# NUWC_Ballast_Sensor_Power_Interface_Boar.net
KiCad netlist of a schematic drawn in Altium Designer
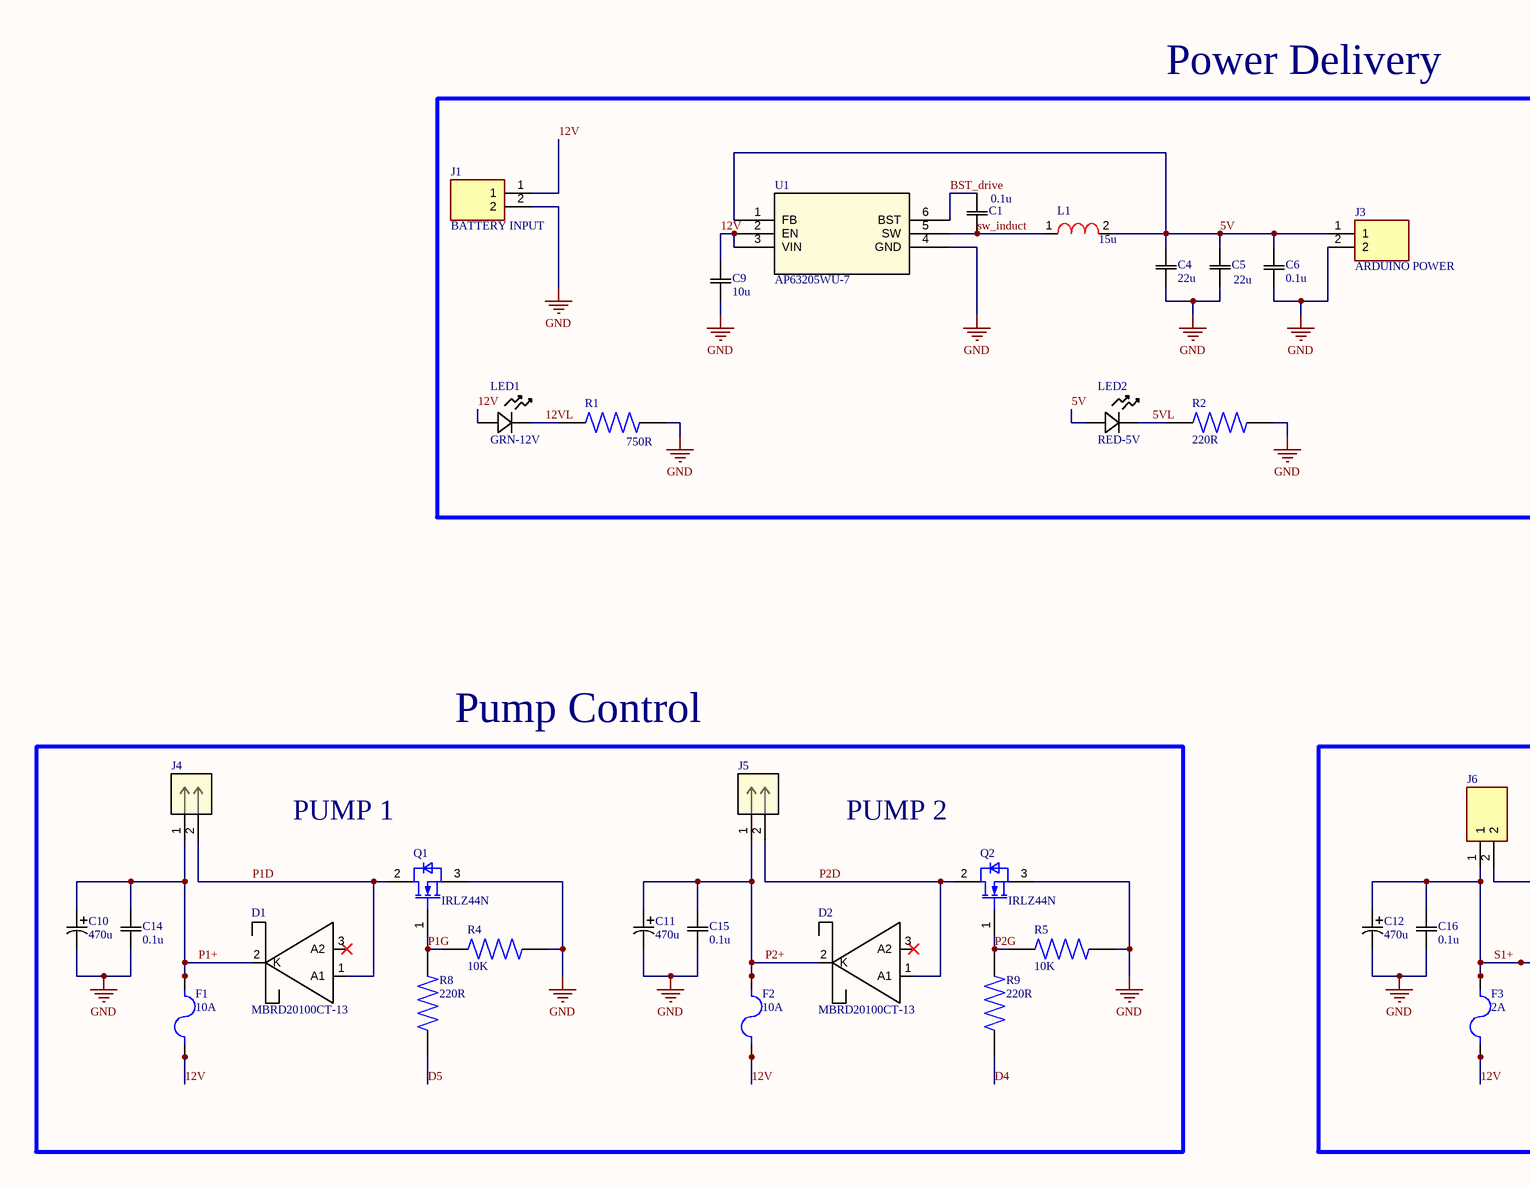
[diagram p0: NUWC_Ballast_Sensor_Power_Interface_Board.SchDoc, top left]
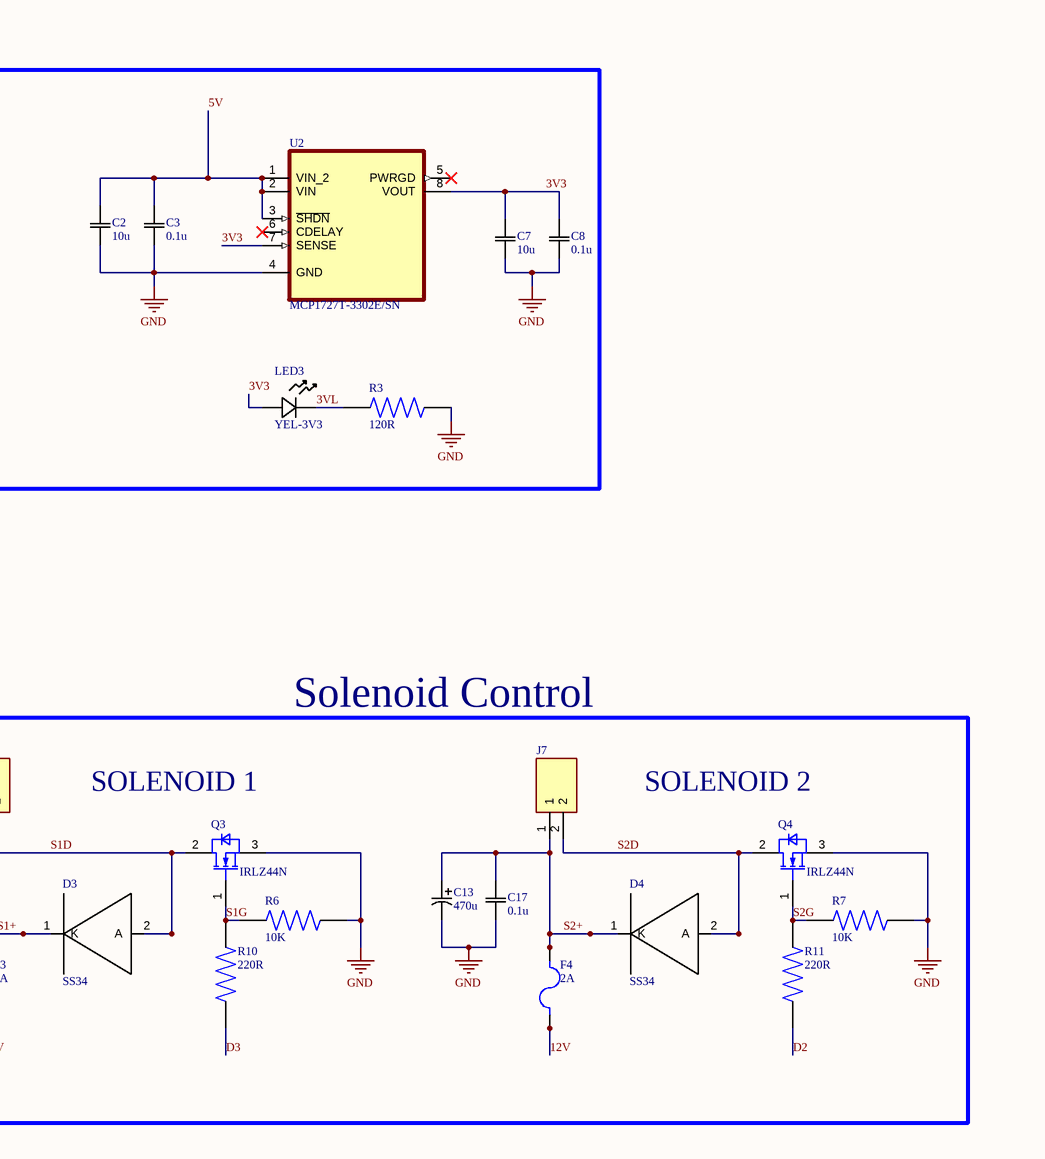
[diagram p1: NUWC_Ballast_Sensor_Power_Interface_Board.SchDoc, top right]
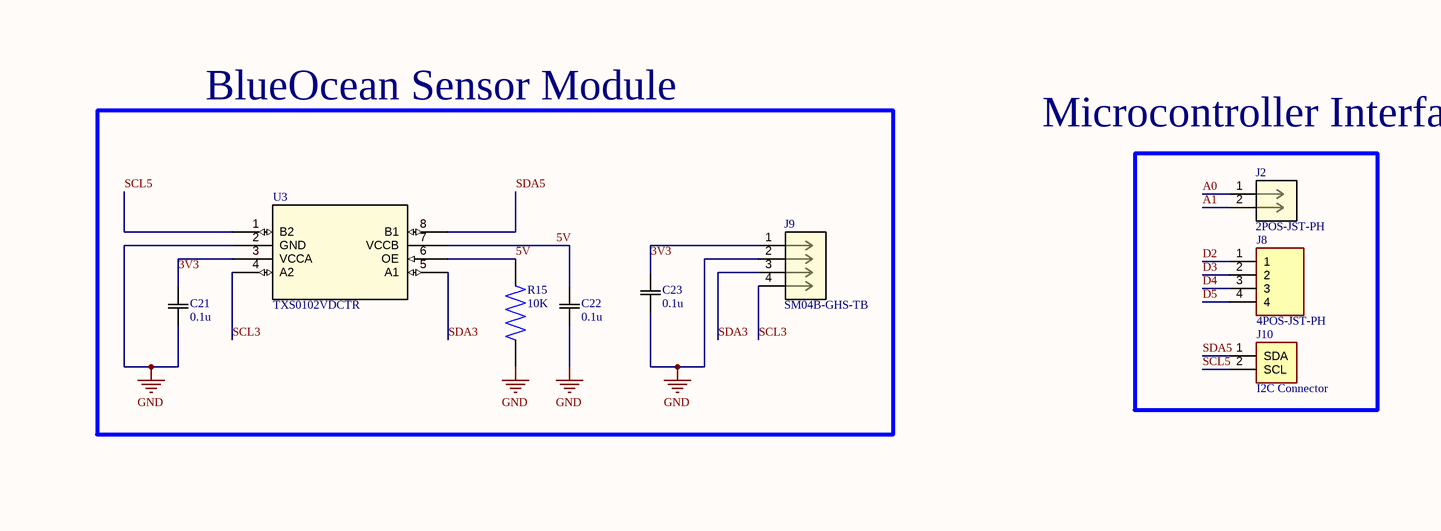
[diagram p2: NUWC_Ballast_Sensor_Power_Interface_Board.SchDoc, bottom left]
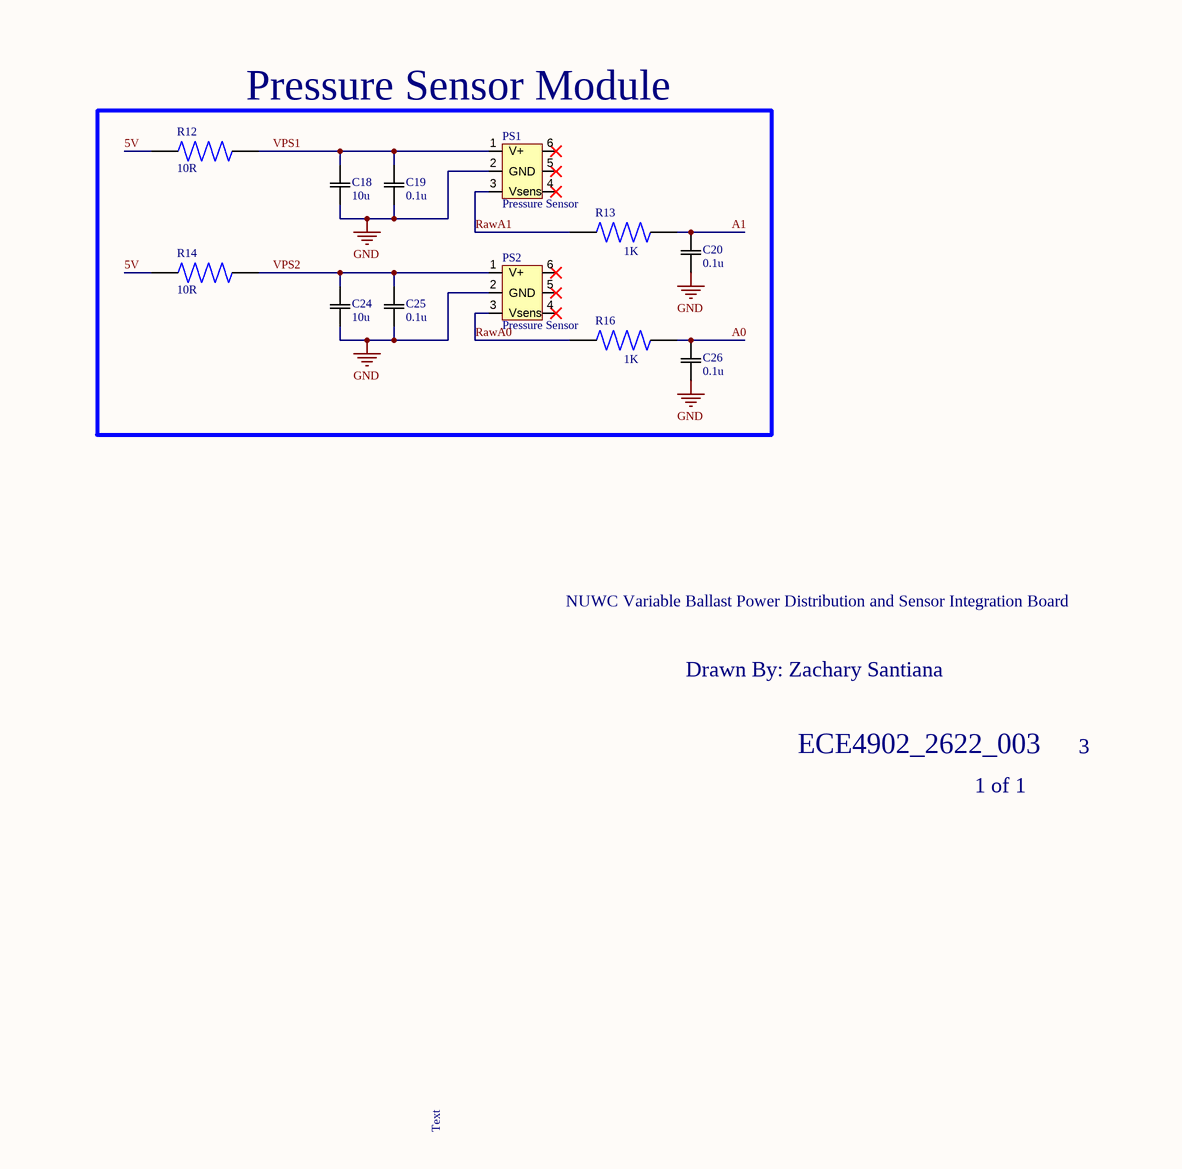
[diagram p3: NUWC_Ballast_Sensor_Power_Interface_Board.SchDoc, bottom right]

(export (version "E")
  (design (tool "Eeschema 10.0.6"))
  (components
    (comp (ref "C1")
      (value "0.1u")
      (footprint "CAP_0805_KEMET")
      (description "Capacitor;Ceramic;Cap;.0.1uF;Tol 10%;SMT;Vol-Rtg 25V;X7R;Tape and Reel ¦ KEMET C0805C104K3RACTU")
      (fields (field (name "MF") "KEMET") (field (name "MP") "C0805C104K3RACTU"))
      (libsource (lib "NUWCBallastBOMSymbols") (part "C0805C104K3RACTU"))
    )
    (comp (ref "C2")
      (value "10u")
      (footprint "CAP_0805_KEMET")
      (description "Capacitor;Ceramic;Cap;.10uF;Tol 10%;SMT;Vol-Rtg 25V;X5R;Tape and Reel ¦ KEMET C0805C106K3PACTU")
      (fields (field (name "MF") "KEMET") (field (name "MP") "C0805C106K3PACTU"))
      (libsource (lib "NUWCBallastBOMSymbols") (part "C0805C106K3PACTU"))
    )
    (comp (ref "C3")
      (value "0.1u")
      (footprint "CAP_0805_KEMET")
      (description "Capacitor;Ceramic;Cap;.0.1uF;Tol 10%;SMT;Vol-Rtg 25V;X7R;Tape and Reel ¦ KEMET C0805C104K3RACTU")
      (fields (field (name "MF") "KEMET") (field (name "MP") "C0805C104K3RACTU"))
      (libsource (lib "NUWCBallastBOMSymbols") (part "C0805C104K3RACTU"))
    )
    (comp (ref "C4")
      (value "22u")
      (footprint "CAP_0805_SAMSUNG")
      (description "Multilayer Ceramic Capacitors MLCC - SMD/SMT 22uF+/-20% 25V X5R 2012")
      (fields (field (name "MF") "Samsung Electro-Mechanics") (field (name "MP") "CL21A226MAYNNNE"))
      (libsource (lib "NUWCBallastBOMSymbols") (part "CL21A226MAYNNNE"))
    )
    (comp (ref "C5")
      (value "22u")
      (footprint "CAP_0805_SAMSUNG")
      (description "Multilayer Ceramic Capacitors MLCC - SMD/SMT 22uF+/-20% 25V X5R 2012")
      (fields (field (name "MF") "Samsung Electro-Mechanics") (field (name "MP") "CL21A226MAYNNNE"))
      (libsource (lib "NUWCBallastBOMSymbols") (part "CL21A226MAYNNNE"))
    )
    (comp (ref "C6")
      (value "0.1u")
      (footprint "CAP_0805_KEMET")
      (description "Capacitor;Ceramic;Cap;.0.1uF;Tol 10%;SMT;Vol-Rtg 25V;X7R;Tape and Reel ¦ KEMET C0805C104K3RACTU")
      (fields (field (name "MF") "KEMET") (field (name "MP") "C0805C104K3RACTU"))
      (libsource (lib "NUWCBallastBOMSymbols") (part "C0805C104K3RACTU"))
    )
    (comp (ref "C7")
      (value "10u")
      (footprint "CAP_0805_KEMET")
      (description "Capacitor;Ceramic;Cap;.10uF;Tol 10%;SMT;Vol-Rtg 25V;X5R;Tape and Reel ¦ KEMET C0805C106K3PACTU")
      (fields (field (name "MF") "KEMET") (field (name "MP") "C0805C106K3PACTU"))
      (libsource (lib "NUWCBallastBOMSymbols") (part "C0805C106K3PACTU"))
    )
    (comp (ref "C8")
      (value "0.1u")
      (footprint "CAP_0805_KEMET")
      (description "Capacitor;Ceramic;Cap;.0.1uF;Tol 10%;SMT;Vol-Rtg 25V;X7R;Tape and Reel ¦ KEMET C0805C104K3RACTU")
      (fields (field (name "MF") "KEMET") (field (name "MP") "C0805C104K3RACTU"))
      (libsource (lib "NUWCBallastBOMSymbols") (part "C0805C104K3RACTU"))
    )
    (comp (ref "C9")
      (value "10u")
      (footprint "CAP_0805_KEMET")
      (description "Capacitor;Ceramic;Cap;.10uF;Tol 10%;SMT;Vol-Rtg 25V;X5R;Tape and Reel ¦ KEMET C0805C106K3PACTU")
      (fields (field (name "MF") "KEMET") (field (name "MP") "C0805C106K3PACTU"))
      (libsource (lib "NUWCBallastBOMSymbols") (part "C0805C106K3PACTU"))
    )
    (comp (ref "C10")
      (value "470u")
      (footprint "PCAP_10x10-ELECT_NCA")
      (fields
        (field (name "MANUFACTURER_PART_NUMBER") "UWT1E471MNL1GS")
        (field (name "COPYRIGHT") "Copyright (C) 2025 Ultra Librarian. All rights reserved.")
      )
      (libsource (lib "NUWCBallastBOMSymbols") (part "UWT1E471MNL1GS_1"))
    )
    (comp (ref "C11")
      (value "470u")
      (footprint "PCAP_10x10-ELECT_NCA")
      (fields
        (field (name "MANUFACTURER_PART_NUMBER") "UWT1E471MNL1GS")
        (field (name "COPYRIGHT") "Copyright (C) 2025 Ultra Librarian. All rights reserved.")
      )
      (libsource (lib "NUWCBallastBOMSymbols") (part "UWT1E471MNL1GS_1"))
    )
    (comp (ref "C12")
      (value "470u")
      (footprint "PCAP_10x10-ELECT_NCA")
      (fields
        (field (name "MANUFACTURER_PART_NUMBER") "UWT1E471MNL1GS")
        (field (name "COPYRIGHT") "Copyright (C) 2025 Ultra Librarian. All rights reserved.")
      )
      (libsource (lib "NUWCBallastBOMSymbols") (part "UWT1E471MNL1GS_1"))
    )
    (comp (ref "C13")
      (value "470u")
      (footprint "PCAP_10x10-ELECT_NCA")
      (fields
        (field (name "MANUFACTURER_PART_NUMBER") "UWT1E471MNL1GS")
        (field (name "COPYRIGHT") "Copyright (C) 2025 Ultra Librarian. All rights reserved.")
      )
      (libsource (lib "NUWCBallastBOMSymbols") (part "UWT1E471MNL1GS_1"))
    )
    (comp (ref "C14")
      (value "0.1u")
      (footprint "CAP_0805_KEMET")
      (description "Capacitor;Ceramic;Cap;.0.1uF;Tol 10%;SMT;Vol-Rtg 25V;X7R;Tape and Reel ¦ KEMET C0805C104K3RACTU")
      (fields (field (name "MF") "KEMET") (field (name "MP") "C0805C104K3RACTU"))
      (libsource (lib "NUWCBallastBOMSymbols") (part "C0805C104K3RACTU"))
    )
    (comp (ref "C15")
      (value "0.1u")
      (footprint "CAP_0805_KEMET")
      (description "Capacitor;Ceramic;Cap;.0.1uF;Tol 10%;SMT;Vol-Rtg 25V;X7R;Tape and Reel ¦ KEMET C0805C104K3RACTU")
      (fields (field (name "MF") "KEMET") (field (name "MP") "C0805C104K3RACTU"))
      (libsource (lib "NUWCBallastBOMSymbols") (part "C0805C104K3RACTU"))
    )
    (comp (ref "C16")
      (value "0.1u")
      (footprint "CAP_0805_KEMET")
      (description "Capacitor;Ceramic;Cap;.0.1uF;Tol 10%;SMT;Vol-Rtg 25V;X7R;Tape and Reel ¦ KEMET C0805C104K3RACTU")
      (fields (field (name "MF") "KEMET") (field (name "MP") "C0805C104K3RACTU"))
      (libsource (lib "NUWCBallastBOMSymbols") (part "C0805C104K3RACTU"))
    )
    (comp (ref "C17")
      (value "0.1u")
      (footprint "CAP_0805_KEMET")
      (description "Capacitor;Ceramic;Cap;.0.1uF;Tol 10%;SMT;Vol-Rtg 25V;X7R;Tape and Reel ¦ KEMET C0805C104K3RACTU")
      (fields (field (name "MF") "KEMET") (field (name "MP") "C0805C104K3RACTU"))
      (libsource (lib "NUWCBallastBOMSymbols") (part "C0805C104K3RACTU"))
    )
    (comp (ref "C18")
      (value "10u")
      (footprint "CAP_0805_KEMET")
      (description "Capacitor;Ceramic;Cap;.10uF;Tol 10%;SMT;Vol-Rtg 25V;X5R;Tape and Reel ¦ KEMET C0805C106K3PACTU")
      (fields (field (name "MF") "KEMET") (field (name "MP") "C0805C106K3PACTU"))
      (libsource (lib "NUWCBallastBOMSymbols") (part "C0805C106K3PACTU"))
    )
    (comp (ref "C19")
      (value "0.1u")
      (footprint "CAP_0805_KEMET")
      (description "Capacitor;Ceramic;Cap;.0.1uF;Tol 10%;SMT;Vol-Rtg 25V;X7R;Tape and Reel ¦ KEMET C0805C104K3RACTU")
      (fields (field (name "MF") "KEMET") (field (name "MP") "C0805C104K3RACTU"))
      (libsource (lib "NUWCBallastBOMSymbols") (part "C0805C104K3RACTU"))
    )
    (comp (ref "C20")
      (value "0.1u")
      (footprint "CAP_0805_KEMET")
      (description "Capacitor;Ceramic;Cap;.0.1uF;Tol 10%;SMT;Vol-Rtg 25V;X7R;Tape and Reel ¦ KEMET C0805C104K3RACTU")
      (fields (field (name "MF") "KEMET") (field (name "MP") "C0805C104K3RACTU"))
      (libsource (lib "NUWCBallastBOMSymbols") (part "C0805C104K3RACTU"))
    )
    (comp (ref "C21")
      (value "0.1u")
      (footprint "CAP_0805_KEMET")
      (description "Capacitor;Ceramic;Cap;.0.1uF;Tol 10%;SMT;Vol-Rtg 25V;X7R;Tape and Reel ¦ KEMET C0805C104K3RACTU")
      (fields (field (name "MF") "KEMET") (field (name "MP") "C0805C104K3RACTU"))
      (libsource (lib "NUWCBallastBOMSymbols") (part "C0805C104K3RACTU"))
    )
    (comp (ref "C22")
      (value "0.1u")
      (footprint "CAP_0805_KEMET")
      (description "Capacitor;Ceramic;Cap;.0.1uF;Tol 10%;SMT;Vol-Rtg 25V;X7R;Tape and Reel ¦ KEMET C0805C104K3RACTU")
      (fields (field (name "MF") "KEMET") (field (name "MP") "C0805C104K3RACTU"))
      (libsource (lib "NUWCBallastBOMSymbols") (part "C0805C104K3RACTU"))
    )
    (comp (ref "C23")
      (value "0.1u")
      (footprint "CAP_0805_KEMET")
      (description "Capacitor;Ceramic;Cap;.0.1uF;Tol 10%;SMT;Vol-Rtg 25V;X7R;Tape and Reel ¦ KEMET C0805C104K3RACTU")
      (fields (field (name "MF") "KEMET") (field (name "MP") "C0805C104K3RACTU"))
      (libsource (lib "NUWCBallastBOMSymbols") (part "C0805C104K3RACTU"))
    )
    (comp (ref "C24")
      (value "10u")
      (footprint "CAP_0805_KEMET")
      (description "Capacitor;Ceramic;Cap;.10uF;Tol 10%;SMT;Vol-Rtg 25V;X5R;Tape and Reel ¦ KEMET C0805C106K3PACTU")
      (fields (field (name "MF") "KEMET") (field (name "MP") "C0805C106K3PACTU"))
      (libsource (lib "NUWCBallastBOMSymbols") (part "C0805C106K3PACTU"))
    )
    (comp (ref "C25")
      (value "0.1u")
      (footprint "CAP_0805_KEMET")
      (description "Capacitor;Ceramic;Cap;.0.1uF;Tol 10%;SMT;Vol-Rtg 25V;X7R;Tape and Reel ¦ KEMET C0805C104K3RACTU")
      (fields (field (name "MF") "KEMET") (field (name "MP") "C0805C104K3RACTU"))
      (libsource (lib "NUWCBallastBOMSymbols") (part "C0805C104K3RACTU"))
    )
    (comp (ref "C26")
      (value "0.1u")
      (footprint "CAP_0805_KEMET")
      (description "Capacitor;Ceramic;Cap;.0.1uF;Tol 10%;SMT;Vol-Rtg 25V;X7R;Tape and Reel ¦ KEMET C0805C104K3RACTU")
      (fields (field (name "MF") "KEMET") (field (name "MP") "C0805C104K3RACTU"))
      (libsource (lib "NUWCBallastBOMSymbols") (part "C0805C104K3RACTU"))
    )
    (comp (ref "D1")
      (value "MBRD20100CT-13")
      (footprint "MBRD20100CT_SHOT_DIODE")
      (description "DIODE ARR SCHOT 100V 10A TO2523\r\nDiodes Incorporated")
      (libsource (lib "NUWCBallastBOMSymbols") (part "MBRD20100CT-13"))
    )
    (comp (ref "D2")
      (value "MBRD20100CT-13")
      (footprint "MBRD20100CT_SHOT_DIODE")
      (description "DIODE ARR SCHOT 100V 10A TO2523\r\nDiodes Incorporated")
      (libsource (lib "NUWCBallastBOMSymbols") (part "MBRD20100CT-13"))
    )
    (comp (ref "D3")
      (value "SS34")
      (footprint "SHOTT_DIODE")
      (description "Description")
      (fields (field (name "COPYRIGHT") "Copyright (C) 2025 Ultra Librarian. All rights reserved."))
      (libsource (lib "NUWCBallastBOMSymbols") (part "SS34"))
    )
    (comp (ref "D4")
      (value "SS34")
      (footprint "SHOTT_DIODE")
      (description "Description")
      (fields (field (name "COPYRIGHT") "Copyright (C) 2025 Ultra Librarian. All rights reserved."))
      (libsource (lib "NUWCBallastBOMSymbols") (part "SS34"))
    )
    (comp (ref "F1")
      (value "10A")
      (footprint "FUSE_3557-2")
      (description "THM 2 in 1 Auto Blade Holder")
      (fields (field (name "MF") "Keystone Electronics") (field (name "MP") "3557-2"))
      (libsource (lib "NUWCBallastBOMSymbols") (part "3557-2"))
    )
    (comp (ref "F2")
      (value "10A")
      (footprint "FUSE_3557-2")
      (description "THM 2 in 1 Auto Blade Holder")
      (fields (field (name "MF") "Keystone Electronics") (field (name "MP") "3557-2"))
      (libsource (lib "NUWCBallastBOMSymbols") (part "3557-2"))
    )
    (comp (ref "F3")
      (value "2A")
      (footprint "FUSE_3557-2")
      (description "THM 2 in 1 Auto Blade Holder")
      (fields (field (name "MF") "Keystone Electronics") (field (name "MP") "3557-2"))
      (libsource (lib "NUWCBallastBOMSymbols") (part "3557-2"))
    )
    (comp (ref "F4")
      (value "2A")
      (footprint "FUSE_3557-2")
      (description "THM 2 in 1 Auto Blade Holder")
      (fields (field (name "MF") "Keystone Electronics") (field (name "MP") "3557-2"))
      (libsource (lib "NUWCBallastBOMSymbols") (part "3557-2"))
    )
    (comp (ref "J1")
      (value "BATTERY INPUT")
      (footprint "CUI_TBP02R1-381-02BE")
      (description "2~24 Poles, Pluggable,Receptacle, Horizontal, 3.81 Pitch, Terminal Block Connector")
      (fields (field (name "MF") "Same Sky") (field (name "MP") "TBP02R1-381-02BE"))
      (libsource (lib "") (part "TBP02R1-381-02BE_1"))
    )
    (comp (ref "J2")
      (value "2POS-JST-PH")
      (footprint "JST_S2B-PH-SM4-TB")
      (libsource (lib "NUWCBallastBOMSymbols") (part "JST_PH_2POS_SMD_RA"))
    )
    (comp (ref "J3")
      (value "ARDUINO POWER")
      (footprint "CUI_TBP02R1-381-02BE")
      (description "2~24 Poles, Pluggable,Receptacle, Horizontal, 3.81 Pitch, Terminal Block Connector")
      (fields (field (name "MF") "Same Sky") (field (name "MP") "TBP02R1-381-02BE"))
      (libsource (lib "NUWCBallastBOMSymbols") (part "TBP02R1-381-02BE"))
    )
    (comp (ref "J4")
      (value "26607020")
      (footprint "CONN_SD-42892-001_M450_02_MOL")
      (fields (field (name "COPYRIGHT") "Copyright (C) 2026 Ultra Librarian. All rights reserved."))
      (libsource (lib "NUWCBallastBOMSymbols") (part "26607020"))
    )
    (comp (ref "J5")
      (value "26607020")
      (footprint "CONN_SD-42892-001_M450_02_MOL")
      (fields (field (name "COPYRIGHT") "Copyright (C) 2026 Ultra Librarian. All rights reserved."))
      (libsource (lib "NUWCBallastBOMSymbols") (part "26607020"))
    )
    (comp (ref "J6")
      (value "BATTERY INPUT")
      (footprint "CUI_TBP02R1-381-02BE")
      (description "2~24 Poles, Pluggable,Receptacle, Horizontal, 3.81 Pitch, Terminal Block Connector")
      (fields (field (name "MF") "Same Sky") (field (name "MP") "TBP02R1-381-02BE"))
      (libsource (lib "") (part "TBP02R1-381-02BE_2"))
    )
    (comp (ref "J7")
      (value "BATTERY INPUT")
      (footprint "CUI_TBP02R1-381-02BE")
      (description "2~24 Poles, Pluggable,Receptacle, Horizontal, 3.81 Pitch, Terminal Block Connector")
      (fields (field (name "MF") "Same Sky") (field (name "MP") "TBP02R1-381-02BE"))
      (libsource (lib "") (part "TBP02R1-381-02BE_2"))
    )
    (comp (ref "J8")
      (value "4POS-JST-PH")
      (footprint "JST_S4B-PH-SM4-TB")
      (description "Connector Header Surface Mount, Right Angle 4 position 0.079 (2.00mm)")
      (fields (field (name "MF") "JST Sales") (field (name "MP") "S4B-PH-SM4-TB"))
      (libsource (lib "NUWCBallastBOMSymbols") (part "S4B-PH-SM4-TB"))
    )
    (comp (ref "J9")
      (value "SM04B-GHS-TB")
      (footprint "CONN_SM04B-GHS-TB_JST")
      (description "Description")
      (fields (field (name "COPYRIGHT") "Copyright (C) 2025 Ultra Librarian. All rights reserved."))
      (libsource (lib "NUWCBallastBOMSymbols") (part "SM04B-GHS-TB"))
    )
    (comp (ref "J10")
      (value "I2C Connector")
      (footprint "MOLEX_530470210")
      (description "Connector Header Through Hole 2 position 0.049 (1.25mm)")
      (fields (field (name "DIGI-KEY_PART_NUMBER") "WM1731-ND") (field (name "MP") "530470210"))
      (libsource (lib "NUWCBallastBOMSymbols") (part "I2C Connector"))
    )
    (comp (ref "L1")
      (value "15u")
      (footprint "inductor")
      (libsource (lib "NUWCBallastBOMSymbols") (part "Inductor"))
    )
    (comp (ref "LED1")
      (value "GRN-12V")
      (footprint "LED_LGR971-KN-1_OSR")
      (description "GREEN DIFF LED")
      (fields
        (field (name "MANUFACTURER_PART_NUMBER") "LGR971-KN-1")
        (field (name "COPYRIGHT") "Copyright (C) 2025 Ultra Librarian. All rights reserved.")
      )
      (libsource (lib "NUWCBallastBOMSymbols") (part "LGR971-KN-1"))
    )
    (comp (ref "LED2")
      (value "RED-5V")
      (footprint "LED_LGR971-KN-1_OSR")
      (description "RED DIFF LED")
      (fields
        (field (name "MANUFACTURER_PART_NUMBER") "LGR971-KN-1")
        (field (name "COPYRIGHT") "Copyright (C) 2025 Ultra Librarian. All rights reserved.")
      )
      (libsource (lib "NUWCBallastBOMSymbols") (part "LS R976-NR-1-0-20-R18"))
    )
    (comp (ref "LED3")
      (value "YEL-3V3")
      (footprint "LED_LGR971-KN-1_OSR")
      (description "YEL DIFF LED")
      (fields
        (field (name "MANUFACTURER_PART_NUMBER") "LGR971-KN-1")
        (field (name "COPYRIGHT") "Copyright (C) 2025 Ultra Librarian. All rights reserved.")
      )
      (libsource (lib "NUWCBallastBOMSymbols") (part "LY R976-PS-36-0-20-R18"))
    )
    (comp (ref "PS1")
      (value "Pressure Sensor")
      (footprint "PCBComponent_1")
      (libsource (lib "NUWCBallastBOMSymbols") (part "Pressure Sensor"))
    )
    (comp (ref "PS2")
      (value "Pressure Sensor")
      (footprint "PCBComponent_1")
      (libsource (lib "NUWCBallastBOMSymbols") (part "Pressure Sensor"))
    )
    (comp (ref "Q1")
      (value "IRLZ44N")
      (footprint "IFX-PG-TO220-3-904-1")
      (description "OptiMOS 3 Power-Transistor, VDS 100V")
      (fields (field (name "MANUFACTURER") "Infineon Technologies"))
      (libsource (lib "NUWCBallastBOMSymbols") (part "IRLZ44N"))
    )
    (comp (ref "Q2")
      (value "IRLZ44N")
      (footprint "IFX-PG-TO220-3-904-1")
      (description "OptiMOS 3 Power-Transistor, VDS 100V")
      (fields (field (name "MANUFACTURER") "Infineon Technologies"))
      (libsource (lib "NUWCBallastBOMSymbols") (part "IRLZ44N"))
    )
    (comp (ref "Q3")
      (value "IRLZ44N")
      (footprint "IFX-PG-TO220-3-904-1")
      (description "OptiMOS 3 Power-Transistor, VDS 100V")
      (fields (field (name "MANUFACTURER") "Infineon Technologies"))
      (libsource (lib "NUWCBallastBOMSymbols") (part "IRLZ44N"))
    )
    (comp (ref "Q4")
      (value "IRLZ44N")
      (footprint "IFX-PG-TO220-3-904-1")
      (description "OptiMOS 3 Power-Transistor, VDS 100V")
      (fields (field (name "MANUFACTURER") "Infineon Technologies"))
      (libsource (lib "NUWCBallastBOMSymbols") (part "IRLZ44N"))
    )
    (comp (ref "R1")
      (value "750R")
      (footprint "RESC2012X50N")
      (fields (field (name "MF") "Vishay") (field (name "MP") "CRCW08051K00FKEA"))
      (libsource (lib "NUWCBallastBOMSymbols") (part "CRCW08051K00FKEA"))
    )
    (comp (ref "R2")
      (value "220R")
      (footprint "RESC2012X50N")
      (fields
        (field (name "MF") "Vishay")
        (field (name "MP") "CRCW08051K00FKEA")
        (field (name "Comment") "CRCW0805560RFKEA")
      )
      (libsource (lib "NUWCBallastBOMSymbols") (part "CRCW0805560RFKEA"))
    )
    (comp (ref "R3")
      (value "120R")
      (footprint "RESC2012X50N")
      (fields
        (field (name "MF") "Vishay")
        (field (name "MP") "CRCW08051K00FKEA")
        (field (name "Comment") "CRCW0805120RFKEA")
      )
      (libsource (lib "NUWCBallastBOMSymbols") (part "CRCW0805120RFKEA"))
    )
    (comp (ref "R4")
      (value "10K")
      (footprint "RESC2012X50N")
      (fields
        (field (name "MF") "Vishay")
        (field (name "MP") "CRCW08051K00FKEA")
        (field (name "Comment") "CRCW080510K0FKEA")
      )
      (libsource (lib "NUWCBallastBOMSymbols") (part "CRCW080510K0FKEA"))
    )
    (comp (ref "R5")
      (value "10K")
      (footprint "RESC2012X50N")
      (fields
        (field (name "MF") "Vishay")
        (field (name "MP") "CRCW08051K00FKEA")
        (field (name "Comment") "CRCW080510K0FKEA")
      )
      (libsource (lib "NUWCBallastBOMSymbols") (part "CRCW080510K0FKEA"))
    )
    (comp (ref "R6")
      (value "10K")
      (footprint "RESC2012X50N")
      (fields
        (field (name "MF") "Vishay")
        (field (name "MP") "CRCW08051K00FKEA")
        (field (name "Comment") "CRCW080510K0FKEA")
      )
      (libsource (lib "NUWCBallastBOMSymbols") (part "CRCW080510K0FKEA"))
    )
    (comp (ref "R7")
      (value "10K")
      (footprint "RESC2012X50N")
      (fields
        (field (name "MF") "Vishay")
        (field (name "MP") "CRCW08051K00FKEA")
        (field (name "Comment") "CRCW080510K0FKEA")
      )
      (libsource (lib "NUWCBallastBOMSymbols") (part "CRCW080510K0FKEA"))
    )
    (comp (ref "R8")
      (value "220R")
      (footprint "RESC2012X50N")
      (fields
        (field (name "MF") "Vishay")
        (field (name "MP") "CRCW08051K00FKEA")
        (field (name "Comment") "CRCW0805220RFKEA")
      )
      (libsource (lib "NUWCBallastBOMSymbols") (part "CRCW0805220RFKEA"))
    )
    (comp (ref "R9")
      (value "220R")
      (footprint "RESC2012X50N")
      (fields
        (field (name "MF") "Vishay")
        (field (name "MP") "CRCW08051K00FKEA")
        (field (name "Comment") "CRCW0805220RFKEA")
      )
      (libsource (lib "NUWCBallastBOMSymbols") (part "CRCW0805220RFKEA"))
    )
    (comp (ref "R10")
      (value "220R")
      (footprint "RESC2012X50N")
      (fields
        (field (name "MF") "Vishay")
        (field (name "MP") "CRCW08051K00FKEA")
        (field (name "Comment") "CRCW0805220RFKEA")
      )
      (libsource (lib "NUWCBallastBOMSymbols") (part "CRCW0805220RFKEA"))
    )
    (comp (ref "R11")
      (value "220R")
      (footprint "RESC2012X50N")
      (fields
        (field (name "MF") "Vishay")
        (field (name "MP") "CRCW08051K00FKEA")
        (field (name "Comment") "CRCW0805220RFKEA")
      )
      (libsource (lib "NUWCBallastBOMSymbols") (part "CRCW0805220RFKEA"))
    )
    (comp (ref "R12")
      (value "10R")
      (footprint "RESC2012X50N")
      (fields
        (field (name "MF") "Vishay")
        (field (name "MP") "CRCW08051K00FKEA")
        (field (name "Comment") "CRCW080510R0FKEA")
      )
      (libsource (lib "NUWCBallastBOMSymbols") (part "CRCW080510R0FKEA"))
    )
    (comp (ref "R13")
      (value "1K")
      (footprint "RESC2012X50N")
      (fields (field (name "MF") "Vishay") (field (name "MP") "CRCW08051K00FKEA"))
      (libsource (lib "NUWCBallastBOMSymbols") (part "CRCW08051K00FKEA"))
    )
    (comp (ref "R14")
      (value "10R")
      (footprint "RESC2012X50N")
      (fields
        (field (name "MF") "Vishay")
        (field (name "MP") "CRCW08051K00FKEA")
        (field (name "Comment") "CRCW080510R0FKEA")
      )
      (libsource (lib "NUWCBallastBOMSymbols") (part "CRCW080510R0FKEA"))
    )
    (comp (ref "R15")
      (value "10K")
      (footprint "RESC2012X50N")
      (fields
        (field (name "MF") "Vishay")
        (field (name "MP") "CRCW08051K00FKEA")
        (field (name "Comment") "CRCW080510K0FKEA")
      )
      (libsource (lib "NUWCBallastBOMSymbols") (part "CRCW080510K0FKEA"))
    )
    (comp (ref "R16")
      (value "1K")
      (footprint "RESC2012X50N")
      (fields (field (name "MF") "Vishay") (field (name "MP") "CRCW08051K00FKEA"))
      (libsource (lib "NUWCBallastBOMSymbols") (part "CRCW08051K00FKEA"))
    )
    (comp (ref "U1")
      (value "AP63205WU-7")
      (footprint "SOIC_05WU-7_DIO")
      (description "Description")
      (fields (field (name "COPYRIGHT") "Copyright (C) 2025 Ultra Librarian. All rights reserved."))
      (libsource (lib "NUWCBallastBOMSymbols") (part "AP63205WU-7"))
    )
    (comp (ref "U2")
      (value "MCP1727T-3302E/SN")
      (footprint "SOIC127P490X175-8N")
      (description "1.5A CMOS LDO, Vout=3.3V, Extended Temp Range ¦ Microchip Technology Inc. MCP1727T-3302E/SN")
      (fields (field (name "MF") "Microchip Technology"))
      (libsource (lib "NUWCBallastBOMSymbols") (part "MCP1727T-3302E/SN"))
    )
    (comp (ref "U3")
      (value "TXS0102VDCTR")
      (footprint "SSOP8_DCT_TEX")
      (description "Two-bit bidirectional level shifter for open-drain and push-pull applications 8-SSOP -40 to 85")
      (fields (field (name "COPYRIGHT") "Copyright (C) 2025 Ultra Librarian. All rights reserved."))
      (libsource (lib "NUWCBallastBOMSymbols") (part "TXS0102VDCTR"))
    )
  )
  (nets
    (net (code "1") (name "/3V3") (class "Default")
      (node (ref "C21") (pin "2") (pinfunction "2_2") (pintype "passive"))
      (node (ref "C23") (pin "2") (pinfunction "2_2") (pintype "passive"))
      (node (ref "C7") (pin "2") (pinfunction "2_2") (pintype "passive"))
      (node (ref "C8") (pin "2") (pinfunction "2_2") (pintype "passive"))
      (node (ref "J9") (pin "1") (pinfunction "1_1") (pintype "passive"))
      (node (ref "LED3") (pin "2") (pinfunction "2_2") (pintype "passive"))
      (node (ref "U2") (pin "7") (pinfunction "SENSE_7") (pintype "input"))
      (node (ref "U2") (pin "8") (pinfunction "VOUT_8") (pintype "power_in"))
      (node (ref "U3") (pin "3") (pinfunction "VCCA_3") (pintype "power_in"))
    )
    (net (code "2") (name "/3VL") (class "Default")
      (node (ref "LED3") (pin "1") (pinfunction "1_1") (pintype "passive"))
      (node (ref "R3") (pin "1") (pinfunction "1_1") (pintype "passive"))
    )
    (net (code "3") (name "/5V") (class "Default")
      (node (ref "C2") (pin "2") (pinfunction "2_2") (pintype "passive"))
      (node (ref "C22") (pin "1") (pinfunction "1_1") (pintype "passive"))
      (node (ref "C3") (pin "2") (pinfunction "2_2") (pintype "passive"))
      (node (ref "C4") (pin "1") (pinfunction "1_1") (pintype "passive"))
      (node (ref "C5") (pin "1") (pinfunction "1_1") (pintype "passive"))
      (node (ref "C6") (pin "2") (pinfunction "2_2") (pintype "passive"))
      (node (ref "J3") (pin "1") (pinfunction "1_1") (pintype "passive"))
      (node (ref "L1") (pin "2") (pinfunction "2_2") (pintype "passive"))
      (node (ref "LED2") (pin "2") (pinfunction "2_2") (pintype "passive"))
      (node (ref "R12") (pin "1") (pinfunction "1_1") (pintype "passive"))
      (node (ref "R14") (pin "1") (pinfunction "1_1") (pintype "passive"))
      (node (ref "R15") (pin "2") (pinfunction "2_2") (pintype "passive"))
      (node (ref "U1") (pin "1") (pinfunction "FB_1") (pintype "passive"))
      (node (ref "U2") (pin "1") (pinfunction "VIN_2_1") (pintype "power_in"))
      (node (ref "U2") (pin "2") (pinfunction "VIN_2") (pintype "power_in"))
      (node (ref "U2") (pin "3") (pinfunction "~{SHDN}_3") (pintype "input"))
      (node (ref "U3") (pin "6") (pinfunction "OE_6") (pintype "input"))
      (node (ref "U3") (pin "7") (pinfunction "VCCB_7") (pintype "power_in"))
    )
    (net (code "4") (name "/5VL") (class "Default")
      (node (ref "LED2") (pin "1") (pinfunction "1_1") (pintype "passive"))
      (node (ref "R2") (pin "2") (pinfunction "2_2") (pintype "passive"))
    )
    (net (code "5") (name "/12V") (class "Default")
      (node (ref "C9") (pin "2") (pinfunction "2_2") (pintype "passive"))
      (node (ref "F1") (pin "1_1") (pinfunction "1_1_1") (pintype "passive"))
      (node (ref "F1") (pin "1_2") (pinfunction "1_1_2") (pintype "passive"))
      (node (ref "F2") (pin "1_1") (pinfunction "1_1_1") (pintype "passive"))
      (node (ref "F2") (pin "1_2") (pinfunction "1_1_2") (pintype "passive"))
      (node (ref "F3") (pin "1_1") (pinfunction "1_1_1") (pintype "passive"))
      (node (ref "F3") (pin "1_2") (pinfunction "1_1_2") (pintype "passive"))
      (node (ref "F4") (pin "1_1") (pinfunction "1_1_1") (pintype "passive"))
      (node (ref "F4") (pin "1_2") (pinfunction "1_1_2") (pintype "passive"))
      (node (ref "J1") (pin "1") (pinfunction "1_1") (pintype "passive"))
      (node (ref "LED1") (pin "2") (pinfunction "2_2") (pintype "passive"))
      (node (ref "U1") (pin "2") (pinfunction "EN_2") (pintype "passive"))
      (node (ref "U1") (pin "3") (pinfunction "VIN_3") (pintype "passive"))
    )
    (net (code "6") (name "/12VL") (class "Default")
      (node (ref "LED1") (pin "1") (pinfunction "1_1") (pintype "passive"))
      (node (ref "R1") (pin "1") (pinfunction "1_1") (pintype "passive"))
    )
    (net (code "7") (name "/A0") (class "Default")
      (node (ref "C26") (pin "2") (pinfunction "2_2") (pintype "passive"))
      (node (ref "J2") (pin "1") (pinfunction "1_1") (pintype "passive"))
      (node (ref "R16") (pin "2") (pinfunction "2_2") (pintype "passive"))
    )
    (net (code "8") (name "/A1") (class "Default")
      (node (ref "C20") (pin "2") (pinfunction "2_2") (pintype "passive"))
      (node (ref "J2") (pin "2") (pinfunction "2_2") (pintype "passive"))
      (node (ref "R13") (pin "2") (pinfunction "2_2") (pintype "passive"))
    )
    (net (code "9") (name "/BST_drive") (class "Default")
      (node (ref "C1") (pin "1") (pinfunction "1_1") (pintype "passive"))
      (node (ref "U1") (pin "6") (pinfunction "BST_6") (pintype "passive"))
    )
    (net (code "10") (name "/D2") (class "Default")
      (node (ref "J8") (pin "1") (pinfunction "1_1") (pintype "passive"))
      (node (ref "R11") (pin "1") (pinfunction "1_1") (pintype "passive"))
    )
    (net (code "11") (name "/D3") (class "Default")
      (node (ref "J8") (pin "2") (pinfunction "2_2") (pintype "passive"))
      (node (ref "R10") (pin "1") (pinfunction "1_1") (pintype "passive"))
    )
    (net (code "12") (name "/D4") (class "Default")
      (node (ref "J8") (pin "3") (pinfunction "3_3") (pintype "passive"))
      (node (ref "R9") (pin "1") (pinfunction "1_1") (pintype "passive"))
    )
    (net (code "13") (name "/D5") (class "Default")
      (node (ref "J8") (pin "4") (pinfunction "4_4") (pintype "passive"))
      (node (ref "R8") (pin "1") (pinfunction "1_1") (pintype "passive"))
    )
    (net (code "14") (name "/P1+") (class "Default")
      (node (ref "C10") (pin "1") (pinfunction "1_1") (pintype "passive"))
      (node (ref "C14") (pin "2") (pinfunction "2_2") (pintype "passive"))
      (node (ref "D1") (pin "2") (pinfunction "K_2") (pintype "passive"))
      (node (ref "F1") (pin "2_1") (pinfunction "2_2_1") (pintype "passive"))
      (node (ref "F1") (pin "2_2") (pinfunction "2_2_2") (pintype "passive"))
      (node (ref "J4") (pin "1") (pinfunction "1_1") (pintype "passive"))
    )
    (net (code "15") (name "/P1D") (class "Default")
      (node (ref "D1") (pin "1") (pinfunction "A1_1") (pintype "passive"))
      (node (ref "J4") (pin "2") (pinfunction "2_2") (pintype "passive"))
      (node (ref "Q1") (pin "2") (pinfunction "DRAIN_2") (pintype "passive"))
    )
    (net (code "16") (name "/P1G") (class "Default")
      (node (ref "Q1") (pin "1") (pinfunction "GATE_1") (pintype "passive"))
      (node (ref "R4") (pin "1") (pinfunction "1_1") (pintype "passive"))
      (node (ref "R8") (pin "2") (pinfunction "2_2") (pintype "passive"))
    )
    (net (code "17") (name "/P2+") (class "Default")
      (node (ref "C11") (pin "1") (pinfunction "1_1") (pintype "passive"))
      (node (ref "C15") (pin "2") (pinfunction "2_2") (pintype "passive"))
      (node (ref "D2") (pin "2") (pinfunction "K_2") (pintype "passive"))
      (node (ref "F2") (pin "2_1") (pinfunction "2_2_1") (pintype "passive"))
      (node (ref "F2") (pin "2_2") (pinfunction "2_2_2") (pintype "passive"))
      (node (ref "J5") (pin "1") (pinfunction "1_1") (pintype "passive"))
    )
    (net (code "18") (name "/P2D") (class "Default")
      (node (ref "D2") (pin "1") (pinfunction "A1_1") (pintype "passive"))
      (node (ref "J5") (pin "2") (pinfunction "2_2") (pintype "passive"))
      (node (ref "Q2") (pin "2") (pinfunction "DRAIN_2") (pintype "passive"))
    )
    (net (code "19") (name "/P2G") (class "Default")
      (node (ref "Q2") (pin "1") (pinfunction "GATE_1") (pintype "passive"))
      (node (ref "R5") (pin "1") (pinfunction "1_1") (pintype "passive"))
      (node (ref "R9") (pin "2") (pinfunction "2_2") (pintype "passive"))
    )
    (net (code "20") (name "/RawA0") (class "Default")
      (node (ref "PS2") (pin "3") (pinfunction "Vsens_3") (pintype "passive"))
      (node (ref "R16") (pin "1") (pinfunction "1_1") (pintype "passive"))
    )
    (net (code "21") (name "/RawA1") (class "Default")
      (node (ref "PS1") (pin "3") (pinfunction "Vsens_3") (pintype "passive"))
      (node (ref "R13") (pin "1") (pinfunction "1_1") (pintype "passive"))
    )
    (net (code "22") (name "/S1+") (class "Default")
      (node (ref "C12") (pin "1") (pinfunction "1_1") (pintype "passive"))
      (node (ref "C16") (pin "2") (pinfunction "2_2") (pintype "passive"))
      (node (ref "D3") (pin "1") (pinfunction "K_1") (pintype "passive"))
      (node (ref "F3") (pin "2_1") (pinfunction "2_2_1") (pintype "passive"))
      (node (ref "F3") (pin "2_2") (pinfunction "2_2_2") (pintype "passive"))
      (node (ref "J6") (pin "1") (pinfunction "1_1") (pintype "passive"))
    )
    (net (code "23") (name "/S1D") (class "Default")
      (node (ref "D3") (pin "2") (pinfunction "A_2") (pintype "passive"))
      (node (ref "J6") (pin "2") (pinfunction "2_2") (pintype "passive"))
      (node (ref "Q3") (pin "2") (pinfunction "DRAIN_2") (pintype "passive"))
    )
    (net (code "24") (name "/S1G") (class "Default")
      (node (ref "Q3") (pin "1") (pinfunction "GATE_1") (pintype "passive"))
      (node (ref "R10") (pin "2") (pinfunction "2_2") (pintype "passive"))
      (node (ref "R6") (pin "1") (pinfunction "1_1") (pintype "passive"))
    )
    (net (code "25") (name "/S2+") (class "Default")
      (node (ref "C13") (pin "1") (pinfunction "1_1") (pintype "passive"))
      (node (ref "C17") (pin "2") (pinfunction "2_2") (pintype "passive"))
      (node (ref "D4") (pin "1") (pinfunction "K_1") (pintype "passive"))
      (node (ref "F4") (pin "2_1") (pinfunction "2_2_1") (pintype "passive"))
      (node (ref "F4") (pin "2_2") (pinfunction "2_2_2") (pintype "passive"))
      (node (ref "J7") (pin "1") (pinfunction "1_1") (pintype "passive"))
    )
    (net (code "26") (name "/S2D") (class "Default")
      (node (ref "D4") (pin "2") (pinfunction "A_2") (pintype "passive"))
      (node (ref "J7") (pin "2") (pinfunction "2_2") (pintype "passive"))
      (node (ref "Q4") (pin "2") (pinfunction "DRAIN_2") (pintype "passive"))
    )
    (net (code "27") (name "/S2G") (class "Default")
      (node (ref "Q4") (pin "1") (pinfunction "GATE_1") (pintype "passive"))
      (node (ref "R11") (pin "2") (pinfunction "2_2") (pintype "passive"))
      (node (ref "R7") (pin "1") (pinfunction "1_1") (pintype "passive"))
    )
    (net (code "28") (name "/SCL3") (class "Default")
      (node (ref "J9") (pin "4") (pinfunction "4_4") (pintype "passive"))
      (node (ref "U3") (pin "4") (pinfunction "A2_4") (pintype "bidirectional"))
    )
    (net (code "29") (name "/SCL5") (class "Default")
      (node (ref "J10") (pin "2") (pinfunction "SCL_2") (pintype "passive"))
      (node (ref "U3") (pin "1") (pinfunction "B2_1") (pintype "bidirectional"))
    )
    (net (code "30") (name "/SDA3") (class "Default")
      (node (ref "J9") (pin "3") (pinfunction "3_3") (pintype "passive"))
      (node (ref "U3") (pin "5") (pinfunction "A1_5") (pintype "bidirectional"))
    )
    (net (code "31") (name "/SDA5") (class "Default")
      (node (ref "J10") (pin "1") (pinfunction "SDA_1") (pintype "passive"))
      (node (ref "U3") (pin "8") (pinfunction "B1_8") (pintype "bidirectional"))
    )
    (net (code "32") (name "/VPS1") (class "Default")
      (node (ref "C18") (pin "2") (pinfunction "2_2") (pintype "passive"))
      (node (ref "C19") (pin "2") (pinfunction "2_2") (pintype "passive"))
      (node (ref "PS1") (pin "1") (pinfunction "V+_1") (pintype "passive"))
      (node (ref "R12") (pin "2") (pinfunction "2_2") (pintype "passive"))
    )
    (net (code "33") (name "/VPS2") (class "Default")
      (node (ref "C24") (pin "2") (pinfunction "2_2") (pintype "passive"))
      (node (ref "C25") (pin "2") (pinfunction "2_2") (pintype "passive"))
      (node (ref "PS2") (pin "1") (pinfunction "V+_1") (pintype "passive"))
      (node (ref "R14") (pin "2") (pinfunction "2_2") (pintype "passive"))
    )
    (net (code "34") (name "/sw_induct") (class "Default")
      (node (ref "C1") (pin "2") (pinfunction "2_2") (pintype "passive"))
      (node (ref "L1") (pin "1") (pinfunction "1_1") (pintype "passive"))
      (node (ref "U1") (pin "5") (pinfunction "SW_5") (pintype "passive"))
    )
    (net (code "35") (name "GND") (class "Default")
      (node (ref "C10") (pin "2") (pinfunction "2_2") (pintype "passive"))
      (node (ref "C11") (pin "2") (pinfunction "2_2") (pintype "passive"))
      (node (ref "C12") (pin "2") (pinfunction "2_2") (pintype "passive"))
      (node (ref "C13") (pin "2") (pinfunction "2_2") (pintype "passive"))
      (node (ref "C14") (pin "1") (pinfunction "1_1") (pintype "passive"))
      (node (ref "C15") (pin "1") (pinfunction "1_1") (pintype "passive"))
      (node (ref "C16") (pin "1") (pinfunction "1_1") (pintype "passive"))
      (node (ref "C17") (pin "1") (pinfunction "1_1") (pintype "passive"))
      (node (ref "C18") (pin "1") (pinfunction "1_1") (pintype "passive"))
      (node (ref "C19") (pin "1") (pinfunction "1_1") (pintype "passive"))
      (node (ref "C2") (pin "1") (pinfunction "1_1") (pintype "passive"))
      (node (ref "C20") (pin "1") (pinfunction "1_1") (pintype "passive"))
      (node (ref "C21") (pin "1") (pinfunction "1_1") (pintype "passive"))
      (node (ref "C22") (pin "2") (pinfunction "2_2") (pintype "passive"))
      (node (ref "C23") (pin "1") (pinfunction "1_1") (pintype "passive"))
      (node (ref "C24") (pin "1") (pinfunction "1_1") (pintype "passive"))
      (node (ref "C25") (pin "1") (pinfunction "1_1") (pintype "passive"))
      (node (ref "C26") (pin "1") (pinfunction "1_1") (pintype "passive"))
      (node (ref "C3") (pin "1") (pinfunction "1_1") (pintype "passive"))
      (node (ref "C4") (pin "2") (pinfunction "2_2") (pintype "passive"))
      (node (ref "C5") (pin "2") (pinfunction "2_2") (pintype "passive"))
      (node (ref "C6") (pin "1") (pinfunction "1_1") (pintype "passive"))
      (node (ref "C7") (pin "1") (pinfunction "1_1") (pintype "passive"))
      (node (ref "C8") (pin "1") (pinfunction "1_1") (pintype "passive"))
      (node (ref "C9") (pin "1") (pinfunction "1_1") (pintype "passive"))
      (node (ref "J1") (pin "2") (pinfunction "2_2") (pintype "passive"))
      (node (ref "J3") (pin "2") (pinfunction "2_2") (pintype "passive"))
      (node (ref "J9") (pin "2") (pinfunction "2_2") (pintype "passive"))
      (node (ref "PS1") (pin "2") (pinfunction "GND_2") (pintype "passive"))
      (node (ref "PS2") (pin "2") (pinfunction "GND_2") (pintype "passive"))
      (node (ref "Q1") (pin "3") (pinfunction "SOURCE_3") (pintype "passive"))
      (node (ref "Q2") (pin "3") (pinfunction "SOURCE_3") (pintype "passive"))
      (node (ref "Q3") (pin "3") (pinfunction "SOURCE_3") (pintype "passive"))
      (node (ref "Q4") (pin "3") (pinfunction "SOURCE_3") (pintype "passive"))
      (node (ref "R1") (pin "2") (pinfunction "2_2") (pintype "passive"))
      (node (ref "R15") (pin "1") (pinfunction "1_1") (pintype "passive"))
      (node (ref "R2") (pin "1") (pinfunction "1_1") (pintype "passive"))
      (node (ref "R3") (pin "2") (pinfunction "2_2") (pintype "passive"))
      (node (ref "R4") (pin "2") (pinfunction "2_2") (pintype "passive"))
      (node (ref "R5") (pin "2") (pinfunction "2_2") (pintype "passive"))
      (node (ref "R6") (pin "2") (pinfunction "2_2") (pintype "passive"))
      (node (ref "R7") (pin "2") (pinfunction "2_2") (pintype "passive"))
      (node (ref "U1") (pin "4") (pinfunction "GND_4") (pintype "power_in"))
      (node (ref "U2") (pin "4") (pinfunction "GND_4") (pintype "passive"))
      (node (ref "U3") (pin "2") (pinfunction "GND_2") (pintype "power_in"))
    )
    (net (code "36") (name "unconnected-(D1-A2-Pad3)") (class "Default")
      (node (ref "D1") (pin "3") (pinfunction "A2_3") (pintype "passive+no_connect"))
    )
    (net (code "37") (name "unconnected-(D2-A2-Pad3)") (class "Default")
      (node (ref "D2") (pin "3") (pinfunction "A2_3") (pintype "passive+no_connect"))
    )
    (net (code "38") (name "unconnected-(PS1-Pad4)") (class "Default")
      (node (ref "PS1") (pin "4") (pinfunction "4_4") (pintype "passive+no_connect"))
    )
    (net (code "39") (name "unconnected-(PS1-Pad5)") (class "Default")
      (node (ref "PS1") (pin "5") (pinfunction "5_5") (pintype "passive+no_connect"))
    )
    (net (code "40") (name "unconnected-(PS1-Pad6)") (class "Default")
      (node (ref "PS1") (pin "6") (pinfunction "6_6") (pintype "passive+no_connect"))
    )
    (net (code "41") (name "unconnected-(PS2-Pad4)") (class "Default")
      (node (ref "PS2") (pin "4") (pinfunction "4_4") (pintype "passive+no_connect"))
    )
    (net (code "42") (name "unconnected-(PS2-Pad5)") (class "Default")
      (node (ref "PS2") (pin "5") (pinfunction "5_5") (pintype "passive+no_connect"))
    )
    (net (code "43") (name "unconnected-(PS2-Pad6)") (class "Default")
      (node (ref "PS2") (pin "6") (pinfunction "6_6") (pintype "passive+no_connect"))
    )
    (net (code "44") (name "unconnected-(U2-CDELAY-Pad6)") (class "Default")
      (node (ref "U2") (pin "6") (pinfunction "CDELAY_6") (pintype "input+no_connect"))
    )
    (net (code "45") (name "unconnected-(U2-PWRGD-Pad5)") (class "Default")
      (node (ref "U2") (pin "5") (pinfunction "PWRGD_5") (pintype "output+no_connect"))
    )
  )
)
